# pihat.net
KiCad netlist of a schematic drawn in EAGLE
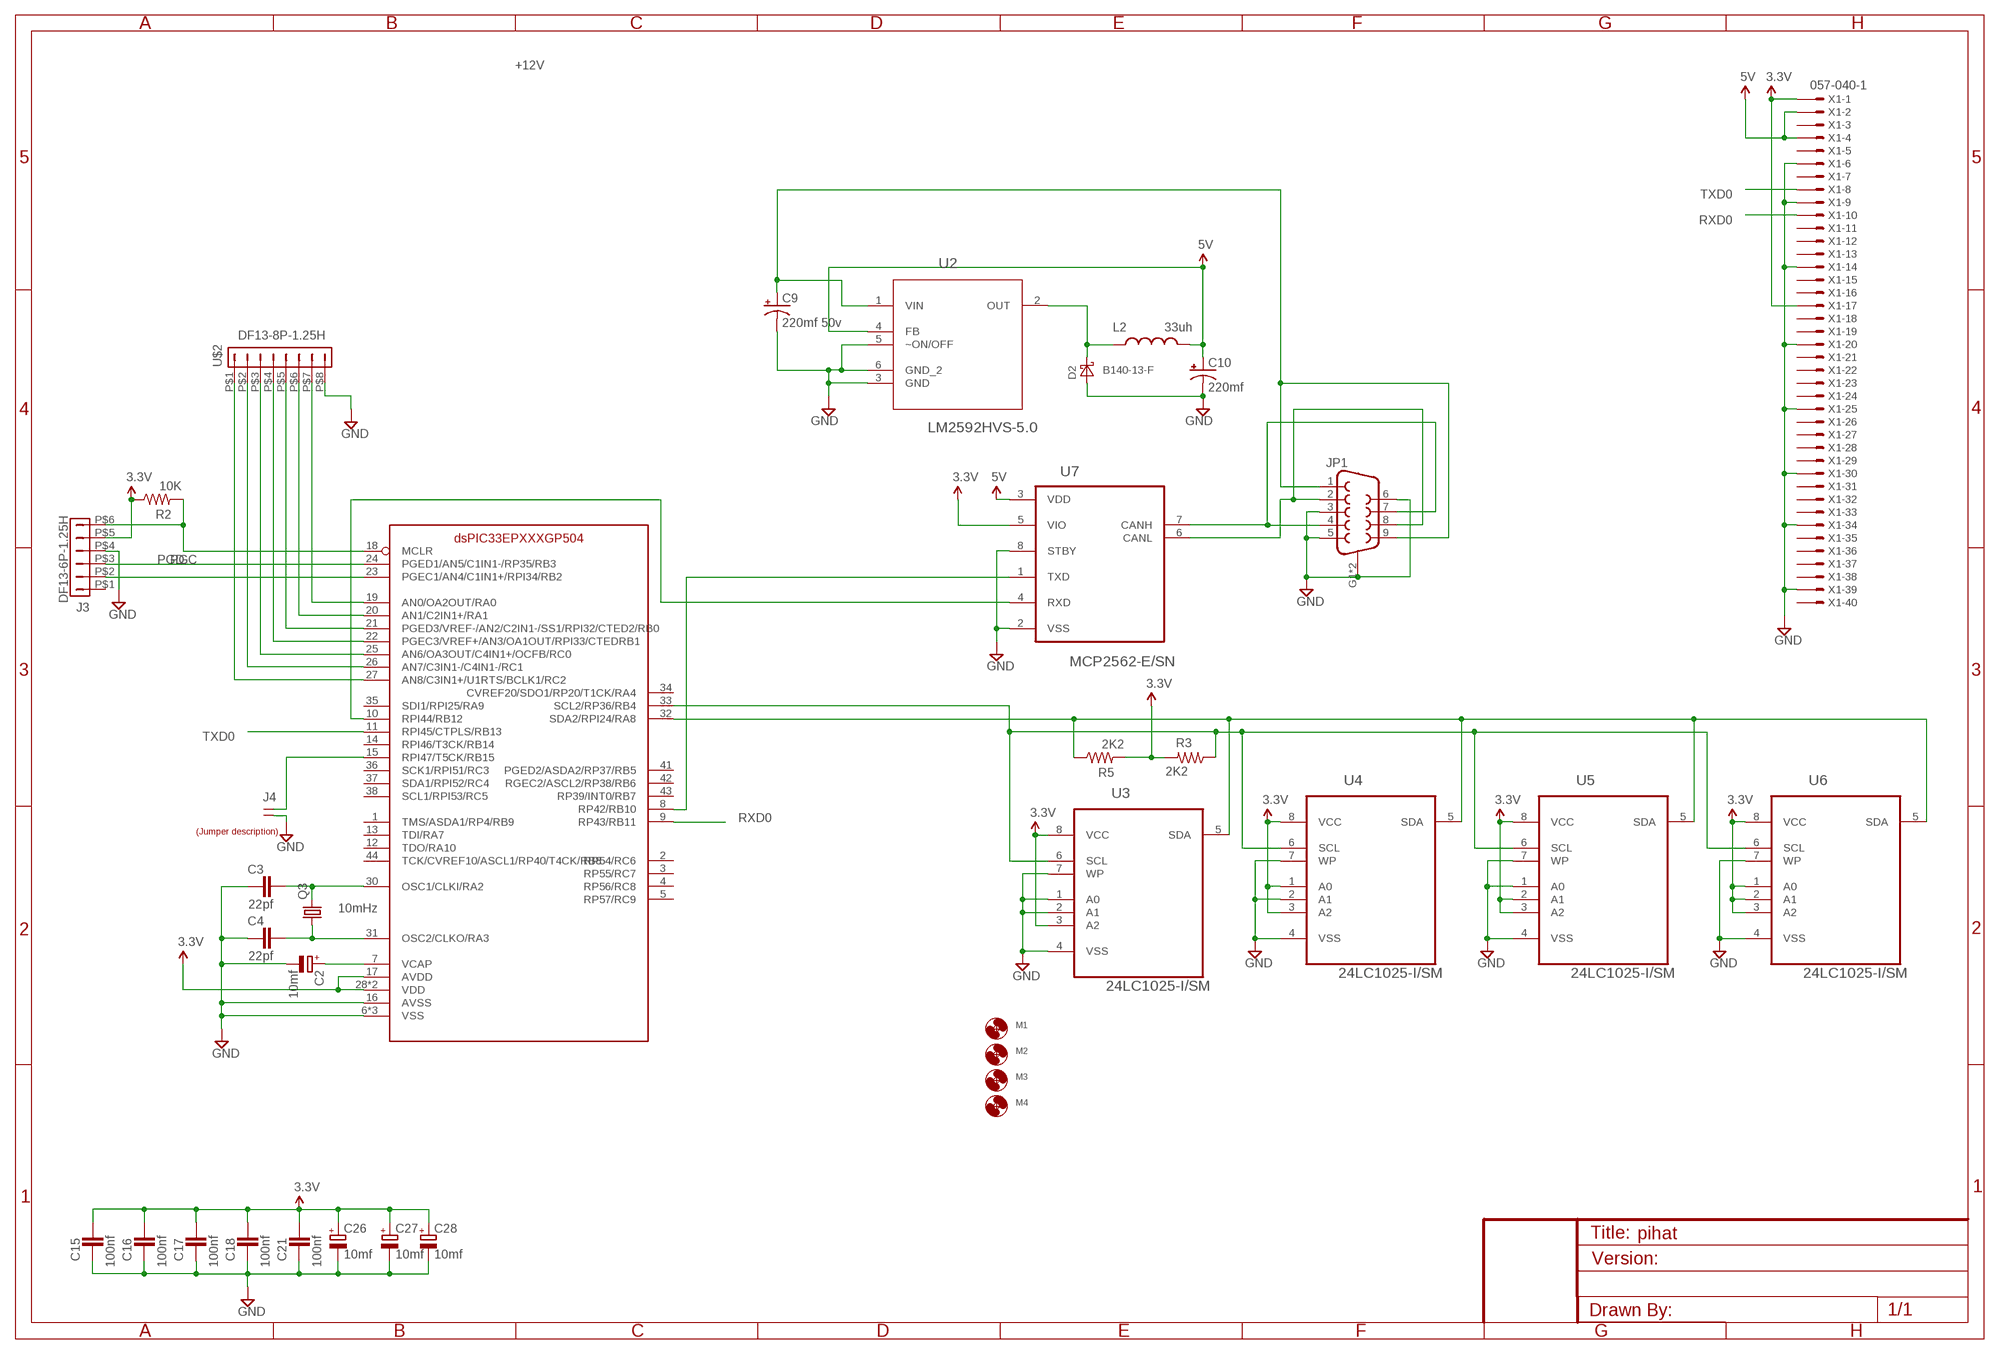
[diagram p0: schematic, sheet 1]

(export (version "E")
  (design (tool "Eeschema 10.0.6"))
  (components
    (comp (ref "C2")
      (value "10mf")
      (footprint "eagle-import:SMC_A")
      (fields (field (name "PARTNO") "T491A106K004AT"))
      (libsource (lib "eagle-import") (part "CAPACITOR_POL-SMC_A"))
    )
    (comp (ref "C3")
      (value "22pf")
      (footprint "eagle-import:C805")
      (fields (field (name "PARTNO") "C0805C220J5GACTU"))
      (libsource (lib "eagle-import") (part "CAPACITOR_NPOL-0805"))
    )
    (comp (ref "C4")
      (value "22pf")
      (footprint "eagle-import:C805")
      (fields (field (name "PARTNO") "C0805C220J5GACTU"))
      (libsource (lib "eagle-import") (part "CAPACITOR_NPOL-0805"))
    )
    (comp (ref "C9")
      (value "220mf 50v")
      (footprint "eagle-import:EIA7343")
      (libsource (lib "eagle-import") (part "CAP_POL7343"))
    )
    (comp (ref "C10")
      (value "220mf")
      (footprint "eagle-import:EIA7343")
      (libsource (lib "eagle-import") (part "CAP_POL7343"))
    )
    (comp (ref "C15")
      (value "100nf")
      (footprint "eagle-import:C805")
      (fields (field (name "PARTNO") "CL21F104ZBCNNNC"))
      (libsource (lib "eagle-import") (part "CAPACITOR_NPOL-0805"))
    )
    (comp (ref "C16")
      (value "100nf")
      (footprint "eagle-import:C805")
      (fields (field (name "PARTNO") "CL21F104ZBCNNNC"))
      (libsource (lib "eagle-import") (part "CAPACITOR_NPOL-0805"))
    )
    (comp (ref "C17")
      (value "100nf")
      (footprint "eagle-import:C805")
      (fields (field (name "PARTNO") "CL21F104ZBCNNNC"))
      (libsource (lib "eagle-import") (part "CAPACITOR_NPOL-0805"))
    )
    (comp (ref "C18")
      (value "100nf")
      (footprint "eagle-import:C805")
      (fields (field (name "PARTNO") "CL21F104ZBCNNNC"))
      (libsource (lib "eagle-import") (part "CAPACITOR_NPOL-0805"))
    )
    (comp (ref "C21")
      (value "100nf")
      (footprint "eagle-import:C805")
      (fields (field (name "PARTNO") "CL21F104ZBCNNNC"))
      (libsource (lib "eagle-import") (part "CAPACITOR_NPOL-0805"))
    )
    (comp (ref "C26")
      (value "10mf")
      (footprint "eagle-import:SMC_A")
      (fields (field (name "PARTNO") "T491A106K004AT"))
      (libsource (lib "eagle-import") (part "CAPACITOR_POL-SMC_A"))
    )
    (comp (ref "C27")
      (value "10mf")
      (footprint "eagle-import:SMC_A")
      (fields (field (name "PARTNO") "T491A106K004AT"))
      (libsource (lib "eagle-import") (part "CAPACITOR_POL-SMC_A"))
    )
    (comp (ref "C28")
      (value "10mf")
      (footprint "eagle-import:SMC_A")
      (fields (field (name "PARTNO") "T491A106K004AT"))
      (libsource (lib "eagle-import") (part "CAPACITOR_POL-SMC_A"))
    )
    (comp (ref "D2")
      (value "B140-13-F")
      (footprint "eagle-import:SMA")
      (libsource (lib "eagle-import") (part "DIODE-SCHOTTKY-SMA"))
    )
    (comp (ref "J3")
      (value "DF13-6P-1.25H")
      (footprint "eagle-import:DF13A-6P-1.25H")
      (fields (field (name "PARTNO") "DF13A-6P-1.25H(20)"))
      (libsource (lib "eagle-import") (part "DF13-6P-1.25H"))
    )
    (comp (ref "J4")
      (value "JUMPER-1X2")
      (footprint "eagle-import:JUMPER-1X2")
      (fields (field (name "PARTNO") "M20-9770246"))
      (libsource (lib "eagle-import") (part "JUMPER-1X2"))
    )
    (comp (ref "JP1")
      (value "DB9MALE")
      (footprint "eagle-import:DB9_MALE")
      (libsource (lib "eagle-import") (part "DB9MALE"))
    )
    (comp (ref "L2")
      (value "33uh")
      (footprint "eagle-import:1812")
      (libsource (lib "eagle-import") (part "INDUCTOR"))
    )
    (comp (ref "M1")
      (value "MOUNT-HOLE2.8")
      (footprint "eagle-import:2,8")
      (libsource (lib "eagle-import") (part "MOUNT-HOLE2.8"))
    )
    (comp (ref "M2")
      (value "MOUNT-HOLE2.8")
      (footprint "eagle-import:2,8")
      (libsource (lib "eagle-import") (part "MOUNT-HOLE2.8"))
    )
    (comp (ref "M3")
      (value "MOUNT-HOLE2.8")
      (footprint "eagle-import:2,8")
      (libsource (lib "eagle-import") (part "MOUNT-HOLE2.8"))
    )
    (comp (ref "M4")
      (value "MOUNT-HOLE2.8")
      (footprint "eagle-import:2,8")
      (libsource (lib "eagle-import") (part "MOUNT-HOLE2.8"))
    )
    (comp (ref "Q3")
      (value "10mHz")
      (footprint "eagle-import:HC49_S")
      (fields (field (name "PARTNO") "ATS100B-E"))
      (libsource (lib "eagle-import") (part "CRYSTALHC49S"))
    )
    (comp (ref "R2")
      (value "10K")
      (footprint "eagle-import:0603-RES")
      (fields (field (name "PARTNO") "RC0603FR-0710KL"))
      (libsource (lib "eagle-import") (part "RESISTOR0603-RES"))
    )
    (comp (ref "R3")
      (value "2K2")
      (footprint "eagle-import:0603-RES")
      (fields (field (name "PARTNO") "RC0603FR-072K2L"))
      (libsource (lib "eagle-import") (part "RESISTOR0603-RES"))
    )
    (comp (ref "R5")
      (value "2K2")
      (footprint "eagle-import:0603-RES")
      (fields (field (name "PARTNO") "RC0603FR-072K2L"))
      (libsource (lib "eagle-import") (part "RESISTOR0603-RES"))
    )
    (comp (ref "U$1")
      (value "LABEL_JUMPER_1X2")
      (footprint "eagle-import:JUMP2_DESC")
      (fields (field (name "OFF") "Normal") (field (name "ON") "Reset"))
      (libsource (lib "eagle-import") (part "LABEL_JUMPER_1X2"))
    )
    (comp (ref "U$2")
      (value "DF13-8P-1.25H")
      (footprint "eagle-import:DF13A-8P-1.25H")
      (libsource (lib "eagle-import") (part "DF13-8P-1.25H"))
    )
    (comp (ref "U1")
      (value "DSPIC33EPXXXGP504")
      (footprint "eagle-import:TQFP44")
      (fields (field (name "PARTNO") "DSPIC33EP512GP504-I/PT"))
      (libsource (lib "eagle-import") (part "DSPIC33EPXXXGP504"))
    )
    (comp (ref "U2")
      (value "LM2592HVS-5.0")
      (footprint "eagle-import:TO170P1435X457-5N")
      (libsource (lib "eagle-import") (part "LM2592HVS-5.0"))
    )
    (comp (ref "U3")
      (value "24LC1025-I/SM")
      (footprint "eagle-import:SOIC8-N_MC")
      (fields (field (name "PARTNO") "24LC1025T-I/SN"))
      (libsource (lib "eagle-import") (part "24LC1025-I/SM"))
    )
    (comp (ref "U4")
      (value "24LC1025-I/SM")
      (footprint "eagle-import:SOIC8-N_MC")
      (fields (field (name "PARTNO") "24LC1025T-I/SN"))
      (libsource (lib "eagle-import") (part "24LC1025-I/SM"))
    )
    (comp (ref "U5")
      (value "24LC1025-I/SM")
      (footprint "eagle-import:SOIC8-N_MC")
      (fields (field (name "PARTNO") "24LC1025T-I/SN"))
      (libsource (lib "eagle-import") (part "24LC1025-I/SM"))
    )
    (comp (ref "U6")
      (value "24LC1025-I/SM")
      (footprint "eagle-import:SOIC8-N_MC")
      (fields (field (name "PARTNO") "24LC1025T-I/SN"))
      (libsource (lib "eagle-import") (part "24LC1025-I/SM"))
    )
    (comp (ref "U7")
      (value "MCP2562-E/SN")
      (footprint "eagle-import:SOIC-8N")
      (libsource (lib "eagle-import") (part "MCP2562-E/SN"))
    )
    (comp (ref "X1")
      (value "057-040-1")
      (footprint "eagle-import:057-040-1")
      (libsource (lib "eagle-import") (part "057-040-1"))
    )
  )
  (nets
    (net (code "1") (name "/+12V") (class "Default")
      (node (ref "C9") (pin "A") (pinfunction "+_A") (pintype "passive"))
      (node (ref "JP1") (pin "1") (pinfunction "1_1") (pintype "passive"))
      (node (ref "JP1") (pin "9") (pinfunction "9_9") (pintype "passive"))
      (node (ref "U2") (pin "1") (pinfunction "VIN_1") (pintype "power_in"))
    )
    (net (code "2") (name "/PGC") (class "Default")
      (node (ref "J3") (pin "P$2") (pinfunction "2_P$2") (pintype "passive"))
      (node (ref "U1") (pin "23") (pinfunction "PGEC1/AN4/C1IN1+/RPI34/RB2_23") (pintype "bidirectional"))
    )
    (net (code "3") (name "/PGD") (class "Default")
      (node (ref "J3") (pin "P$3") (pinfunction "3_P$3") (pintype "passive"))
      (node (ref "U1") (pin "24") (pinfunction "PGED1/AN5/C1IN1-/RP35/RB3_24") (pintype "bidirectional"))
    )
    (net (code "4") (name "/RXD0") (class "Default")
      (node (ref "U1") (pin "9") (pinfunction "RP43/RB11_9") (pintype "bidirectional"))
      (node (ref "X1") (pin "10") (pinfunction "S_10") (pintype "passive"))
    )
    (net (code "5") (name "/TXD0") (class "Default")
      (node (ref "U1") (pin "11") (pinfunction "RPI45/CTPLS/RB13_11") (pintype "bidirectional"))
      (node (ref "X1") (pin "8") (pinfunction "S_8") (pintype "passive"))
    )
    (net (code "6") (name "3.3V") (class "Default")
      (node (ref "C15") (pin "1") (pinfunction "1_1") (pintype "passive"))
      (node (ref "C16") (pin "1") (pinfunction "1_1") (pintype "passive"))
      (node (ref "C17") (pin "1") (pinfunction "1_1") (pintype "passive"))
      (node (ref "C18") (pin "1") (pinfunction "1_1") (pintype "passive"))
      (node (ref "C21") (pin "1") (pinfunction "1_1") (pintype "passive"))
      (node (ref "C26") (pin "+") (pinfunction "+_+") (pintype "passive"))
      (node (ref "C27") (pin "+") (pinfunction "+_+") (pintype "passive"))
      (node (ref "C28") (pin "+") (pinfunction "+_+") (pintype "passive"))
      (node (ref "J3") (pin "P$5") (pinfunction "5_P$5") (pintype "passive"))
      (node (ref "R2") (pin "1") (pinfunction "1_1") (pintype "passive"))
      (node (ref "R3") (pin "2") (pinfunction "2_2") (pintype "passive"))
      (node (ref "R5") (pin "2") (pinfunction "2_2") (pintype "passive"))
      (node (ref "U1") (pin "17") (pinfunction "AVDD_17") (pintype "bidirectional"))
      (node (ref "U1") (pin "28") (pinfunction "VDD_28") (pintype "bidirectional"))
      (node (ref "U1") (pin "40") (pinfunction "VDD_40") (pintype "bidirectional"))
      (node (ref "U3") (pin "3") (pinfunction "A2_3") (pintype "input"))
      (node (ref "U3") (pin "8") (pinfunction "VCC_8") (pintype "power_in"))
      (node (ref "U4") (pin "1") (pinfunction "A0_1") (pintype "input"))
      (node (ref "U4") (pin "3") (pinfunction "A2_3") (pintype "input"))
      (node (ref "U4") (pin "8") (pinfunction "VCC_8") (pintype "power_in"))
      (node (ref "U5") (pin "2") (pinfunction "A1_2") (pintype "input"))
      (node (ref "U5") (pin "3") (pinfunction "A2_3") (pintype "input"))
      (node (ref "U5") (pin "8") (pinfunction "VCC_8") (pintype "power_in"))
      (node (ref "U6") (pin "1") (pinfunction "A0_1") (pintype "input"))
      (node (ref "U6") (pin "2") (pinfunction "A1_2") (pintype "input"))
      (node (ref "U6") (pin "3") (pinfunction "A2_3") (pintype "input"))
      (node (ref "U6") (pin "8") (pinfunction "VCC_8") (pintype "power_in"))
      (node (ref "U7") (pin "5") (pinfunction "VIO_5") (pintype "power_in"))
      (node (ref "X1") (pin "1") (pinfunction "S_1") (pintype "passive"))
      (node (ref "X1") (pin "17") (pinfunction "S_17") (pintype "passive"))
    )
    (net (code "7") (name "5V") (class "Default")
      (node (ref "C10") (pin "A") (pinfunction "+_A") (pintype "passive"))
      (node (ref "L2") (pin "2") (pinfunction "2_2") (pintype "passive"))
      (node (ref "U2") (pin "4") (pinfunction "FB_4") (pintype "input"))
      (node (ref "U7") (pin "3") (pinfunction "VDD_3") (pintype "power_in"))
      (node (ref "X1") (pin "2") (pinfunction "S_2") (pintype "passive"))
      (node (ref "X1") (pin "4") (pinfunction "S_4") (pintype "passive"))
    )
    (net (code "8") (name "GND") (class "Default")
      (node (ref "C10") (pin "C") (pinfunction "-_C") (pintype "passive"))
      (node (ref "C15") (pin "2") (pinfunction "2_2") (pintype "passive"))
      (node (ref "C16") (pin "2") (pinfunction "2_2") (pintype "passive"))
      (node (ref "C17") (pin "2") (pinfunction "2_2") (pintype "passive"))
      (node (ref "C18") (pin "2") (pinfunction "2_2") (pintype "passive"))
      (node (ref "C2") (pin "-") (pinfunction "-_-") (pintype "passive"))
      (node (ref "C21") (pin "2") (pinfunction "2_2") (pintype "passive"))
      (node (ref "C26") (pin "-") (pinfunction "-_-") (pintype "passive"))
      (node (ref "C27") (pin "-") (pinfunction "-_-") (pintype "passive"))
      (node (ref "C28") (pin "-") (pinfunction "-_-") (pintype "passive"))
      (node (ref "C3") (pin "2") (pinfunction "2_2") (pintype "passive"))
      (node (ref "C4") (pin "2") (pinfunction "2_2") (pintype "passive"))
      (node (ref "C9") (pin "C") (pinfunction "-_C") (pintype "passive"))
      (node (ref "D2") (pin "A") (pinfunction "A_A") (pintype "passive"))
      (node (ref "J3") (pin "P$4") (pinfunction "4_P$4") (pintype "passive"))
      (node (ref "J4") (pin "2") (pinfunction "2_2") (pintype "bidirectional"))
      (node (ref "JP1") (pin "3") (pinfunction "3_3") (pintype "passive"))
      (node (ref "JP1") (pin "5") (pinfunction "5_5") (pintype "passive"))
      (node (ref "JP1") (pin "6") (pinfunction "6_6") (pintype "passive"))
      (node (ref "JP1") (pin "G1") (pinfunction "SHIELD_G1") (pintype "power_in"))
      (node (ref "JP1") (pin "G2") (pinfunction "SHIELD_G2") (pintype "power_in"))
      (node (ref "U$2") (pin "P$8") (pinfunction "8_P$8") (pintype "passive"))
      (node (ref "U1") (pin "16") (pinfunction "AVSS_16") (pintype "bidirectional"))
      (node (ref "U1") (pin "29") (pinfunction "VSS_29") (pintype "bidirectional"))
      (node (ref "U1") (pin "39") (pinfunction "VSS_39") (pintype "bidirectional"))
      (node (ref "U1") (pin "6") (pinfunction "VSS_6") (pintype "bidirectional"))
      (node (ref "U2") (pin "3") (pinfunction "GND_3") (pintype "passive"))
      (node (ref "U2") (pin "5") (pinfunction "~{ON/OFF}_5") (pintype "input"))
      (node (ref "U2") (pin "6") (pinfunction "GND_2_6") (pintype "passive"))
      (node (ref "U3") (pin "1") (pinfunction "A0_1") (pintype "input"))
      (node (ref "U3") (pin "2") (pinfunction "A1_2") (pintype "input"))
      (node (ref "U3") (pin "4") (pinfunction "VSS_4") (pintype "passive"))
      (node (ref "U3") (pin "7") (pinfunction "WP_7") (pintype "input"))
      (node (ref "U4") (pin "2") (pinfunction "A1_2") (pintype "input"))
      (node (ref "U4") (pin "4") (pinfunction "VSS_4") (pintype "passive"))
      (node (ref "U4") (pin "7") (pinfunction "WP_7") (pintype "input"))
      (node (ref "U5") (pin "1") (pinfunction "A0_1") (pintype "input"))
      (node (ref "U5") (pin "4") (pinfunction "VSS_4") (pintype "passive"))
      (node (ref "U5") (pin "7") (pinfunction "WP_7") (pintype "input"))
      (node (ref "U6") (pin "4") (pinfunction "VSS_4") (pintype "passive"))
      (node (ref "U6") (pin "7") (pinfunction "WP_7") (pintype "input"))
      (node (ref "U7") (pin "2") (pinfunction "VSS_2") (pintype "power_in"))
      (node (ref "U7") (pin "8") (pinfunction "STBY_8") (pintype "input"))
      (node (ref "X1") (pin "14") (pinfunction "S_14") (pintype "passive"))
      (node (ref "X1") (pin "20") (pinfunction "S_20") (pintype "passive"))
      (node (ref "X1") (pin "25") (pinfunction "S_25") (pintype "passive"))
      (node (ref "X1") (pin "30") (pinfunction "S_30") (pintype "passive"))
      (node (ref "X1") (pin "34") (pinfunction "S_34") (pintype "passive"))
      (node (ref "X1") (pin "39") (pinfunction "S_39") (pintype "passive"))
      (node (ref "X1") (pin "6") (pinfunction "S_6") (pintype "passive"))
      (node (ref "X1") (pin "9") (pinfunction "S_9") (pintype "passive"))
    )
    (net (code "9") (name "Net-(J3-6)") (class "Default")
      (node (ref "J3") (pin "P$6") (pinfunction "6_P$6") (pintype "passive"))
      (node (ref "R2") (pin "2") (pinfunction "2_2") (pintype "passive"))
      (node (ref "U1") (pin "18") (pinfunction "MCLR_18") (pintype "input"))
    )
    (net (code "10") (name "Net-(U$2-1)") (class "Default")
      (node (ref "U$2") (pin "P$1") (pinfunction "1_P$1") (pintype "passive"))
      (node (ref "U1") (pin "27") (pinfunction "AN8/C3IN1+/U1RTS/BCLK1/RC2_27") (pintype "bidirectional"))
    )
    (net (code "11") (name "Net-(U$2-2)") (class "Default")
      (node (ref "U$2") (pin "P$2") (pinfunction "2_P$2") (pintype "passive"))
      (node (ref "U1") (pin "26") (pinfunction "AN7/C3IN1-/C4IN1-/RC1_26") (pintype "bidirectional"))
    )
    (net (code "12") (name "Net-(U$2-3)") (class "Default")
      (node (ref "U$2") (pin "P$3") (pinfunction "3_P$3") (pintype "passive"))
      (node (ref "U1") (pin "25") (pinfunction "AN6/OA3OUT/C4IN1+/OCFB/RC0_25") (pintype "bidirectional"))
    )
    (net (code "13") (name "Net-(U$2-4)") (class "Default")
      (node (ref "U$2") (pin "P$4") (pinfunction "4_P$4") (pintype "passive"))
      (node (ref "U1") (pin "22") (pinfunction "PGEC3/VREF+/AN3/OA1OUT/RPI33/CTEDRB1_22") (pintype "bidirectional"))
    )
    (net (code "14") (name "Net-(U$2-5)") (class "Default")
      (node (ref "U$2") (pin "P$5") (pinfunction "5_P$5") (pintype "passive"))
      (node (ref "U1") (pin "21") (pinfunction "PGED3/VREF-/AN2/C2IN1-/SS1/RPI32/CTED2/RB0_21") (pintype "bidirectional"))
    )
    (net (code "15") (name "Net-(U$2-6)") (class "Default")
      (node (ref "U$2") (pin "P$6") (pinfunction "6_P$6") (pintype "passive"))
      (node (ref "U1") (pin "20") (pinfunction "AN1/C2IN1+/RA1_20") (pintype "bidirectional"))
    )
    (net (code "16") (name "Net-(U$2-7)") (class "Default")
      (node (ref "U$2") (pin "P$7") (pinfunction "7_P$7") (pintype "passive"))
      (node (ref "U1") (pin "19") (pinfunction "AN0/OA2OUT/RA0_19") (pintype "bidirectional"))
    )
    (net (code "17") (name "Net-(U1-OSC1{slash}CLKI{slash}RA2)") (class "Default")
      (node (ref "C3") (pin "1") (pinfunction "1_1") (pintype "passive"))
      (node (ref "Q3") (pin "2") (pinfunction "2_2") (pintype "passive"))
      (node (ref "U1") (pin "30") (pinfunction "OSC1/CLKI/RA2_30") (pintype "bidirectional"))
    )
    (net (code "18") (name "Net-(U1-OSC2{slash}CLKO{slash}RA3)") (class "Default")
      (node (ref "C4") (pin "1") (pinfunction "1_1") (pintype "passive"))
      (node (ref "Q3") (pin "1") (pinfunction "1_1") (pintype "passive"))
      (node (ref "U1") (pin "31") (pinfunction "OSC2/CLKO/RA3_31") (pintype "bidirectional"))
    )
    (net (code "19") (name "Net-(U1-RP42{slash}RB10)") (class "Default")
      (node (ref "U1") (pin "8") (pinfunction "RP42/RB10_8") (pintype "bidirectional"))
      (node (ref "U7") (pin "1") (pinfunction "TXD_1") (pintype "input"))
    )
    (net (code "20") (name "Net-(U1-RPI44{slash}RB12)") (class "Default")
      (node (ref "U1") (pin "10") (pinfunction "RPI44/RB12_10") (pintype "bidirectional"))
      (node (ref "U7") (pin "4") (pinfunction "RXD_4") (pintype "output"))
    )
    (net (code "21") (name "Net-(U1-RPI47{slash}T5CK{slash}RB15)") (class "Default")
      (node (ref "J4") (pin "1") (pinfunction "1_1") (pintype "bidirectional"))
      (node (ref "U1") (pin "15") (pinfunction "RPI47/T5CK/RB15_15") (pintype "bidirectional"))
    )
    (net (code "22") (name "Net-(U1-SCL2{slash}RP36{slash}RB4)") (class "Default")
      (node (ref "R3") (pin "1") (pinfunction "1_1") (pintype "passive"))
      (node (ref "U1") (pin "33") (pinfunction "SCL2/RP36/RB4_33") (pintype "bidirectional"))
      (node (ref "U3") (pin "6") (pinfunction "SCL_6") (pintype "input"))
      (node (ref "U4") (pin "6") (pinfunction "SCL_6") (pintype "input"))
      (node (ref "U5") (pin "6") (pinfunction "SCL_6") (pintype "input"))
      (node (ref "U6") (pin "6") (pinfunction "SCL_6") (pintype "input"))
    )
    (net (code "23") (name "Net-(U1-SDA2{slash}RPI24{slash}RA8)") (class "Default")
      (node (ref "R5") (pin "1") (pinfunction "1_1") (pintype "passive"))
      (node (ref "U1") (pin "32") (pinfunction "SDA2/RPI24/RA8_32") (pintype "bidirectional"))
      (node (ref "U3") (pin "5") (pinfunction "SDA_5") (pintype "bidirectional"))
      (node (ref "U4") (pin "5") (pinfunction "SDA_5") (pintype "bidirectional"))
      (node (ref "U5") (pin "5") (pinfunction "SDA_5") (pintype "bidirectional"))
      (node (ref "U6") (pin "5") (pinfunction "SDA_5") (pintype "bidirectional"))
    )
    (net (code "24") (name "Net-(U1-VCAP)") (class "Default")
      (node (ref "C2") (pin "+") (pinfunction "+_+") (pintype "passive"))
      (node (ref "U1") (pin "7") (pinfunction "VCAP_7") (pintype "bidirectional"))
    )
    (net (code "25") (name "Net-(U2-OUT)") (class "Default")
      (node (ref "D2") (pin "C") (pinfunction "C_C") (pintype "passive"))
      (node (ref "L2") (pin "1") (pinfunction "1_1") (pintype "passive"))
      (node (ref "U2") (pin "2") (pinfunction "OUT_2") (pintype "output"))
    )
    (net (code "26") (name "Net-(U7-CANH)") (class "Default")
      (node (ref "JP1") (pin "4") (pinfunction "4_4") (pintype "passive"))
      (node (ref "JP1") (pin "7") (pinfunction "7_7") (pintype "passive"))
      (node (ref "U7") (pin "7") (pinfunction "CANH_7") (pintype "bidirectional"))
    )
    (net (code "27") (name "Net-(U7-CANL)") (class "Default")
      (node (ref "JP1") (pin "2") (pinfunction "2_2") (pintype "passive"))
      (node (ref "JP1") (pin "8") (pinfunction "8_8") (pintype "passive"))
      (node (ref "U7") (pin "6") (pinfunction "CANL_6") (pintype "bidirectional"))
    )
    (net (code "28") (name "unconnected-(J3-1-PadP$1)") (class "Default")
      (node (ref "J3") (pin "P$1") (pinfunction "1_P$1") (pintype "passive"))
    )
    (net (code "29") (name "unconnected-(U1-CVREF20{slash}SDO1{slash}RP20{slash}T1CK{slash}RA4-Pad34)") (class "Default")
      (node (ref "U1") (pin "34") (pinfunction "CVREF20/SDO1/RP20/T1CK/RA4_34") (pintype "bidirectional"))
    )
    (net (code "30") (name "unconnected-(U1-PGED2{slash}ASDA2{slash}RP37{slash}RB5-Pad41)") (class "Default")
      (node (ref "U1") (pin "41") (pinfunction "PGED2/ASDA2/RP37/RB5_41") (pintype "bidirectional"))
    )
    (net (code "31") (name "unconnected-(U1-RGEC2{slash}ASCL2{slash}RP38{slash}RB6-Pad42)") (class "Default")
      (node (ref "U1") (pin "42") (pinfunction "RGEC2/ASCL2/RP38/RB6_42") (pintype "bidirectional"))
    )
    (net (code "32") (name "unconnected-(U1-RP39{slash}INT0{slash}RB7-Pad43)") (class "Default")
      (node (ref "U1") (pin "43") (pinfunction "RP39/INT0/RB7_43") (pintype "bidirectional"))
    )
    (net (code "33") (name "unconnected-(U1-RP54{slash}RC6-Pad2)") (class "Default")
      (node (ref "U1") (pin "2") (pinfunction "RP54/RC6_2") (pintype "bidirectional"))
    )
    (net (code "34") (name "unconnected-(U1-RP55{slash}RC7-Pad3)") (class "Default")
      (node (ref "U1") (pin "3") (pinfunction "RP55/RC7_3") (pintype "bidirectional"))
    )
    (net (code "35") (name "unconnected-(U1-RP56{slash}RC8-Pad4)") (class "Default")
      (node (ref "U1") (pin "4") (pinfunction "RP56/RC8_4") (pintype "bidirectional"))
    )
    (net (code "36") (name "unconnected-(U1-RP57{slash}RC9-Pad5)") (class "Default")
      (node (ref "U1") (pin "5") (pinfunction "RP57/RC9_5") (pintype "bidirectional"))
    )
    (net (code "37") (name "unconnected-(U1-RPI46{slash}T3CK{slash}RB14-Pad14)") (class "Default")
      (node (ref "U1") (pin "14") (pinfunction "RPI46/T3CK/RB14_14") (pintype "bidirectional"))
    )
    (net (code "38") (name "unconnected-(U1-SCK1{slash}RPI51{slash}RC3-Pad36)") (class "Default")
      (node (ref "U1") (pin "36") (pinfunction "SCK1/RPI51/RC3_36") (pintype "bidirectional"))
    )
    (net (code "39") (name "unconnected-(U1-SCL1{slash}RPI53{slash}RC5-Pad38)") (class "Default")
      (node (ref "U1") (pin "38") (pinfunction "SCL1/RPI53/RC5_38") (pintype "bidirectional"))
    )
    (net (code "40") (name "unconnected-(U1-SDA1{slash}RPI52{slash}RC4-Pad37)") (class "Default")
      (node (ref "U1") (pin "37") (pinfunction "SDA1/RPI52/RC4_37") (pintype "bidirectional"))
    )
    (net (code "41") (name "unconnected-(U1-SDI1{slash}RPI25{slash}RA9-Pad35)") (class "Default")
      (node (ref "U1") (pin "35") (pinfunction "SDI1/RPI25/RA9_35") (pintype "bidirectional"))
    )
    (net (code "42") (name "unconnected-(U1-TCK{slash}CVREF10{slash}ASCL1{slash}RP40{slash}T4CK{slash}RB8-Pad44)") (class "Default")
      (node (ref "U1") (pin "44") (pinfunction "TCK/CVREF10/ASCL1/RP40/T4CK/RB8_44") (pintype "bidirectional"))
    )
    (net (code "43") (name "unconnected-(U1-TDI{slash}RA7-Pad13)") (class "Default")
      (node (ref "U1") (pin "13") (pinfunction "TDI/RA7_13") (pintype "bidirectional"))
    )
    (net (code "44") (name "unconnected-(U1-TDO{slash}RA10-Pad12)") (class "Default")
      (node (ref "U1") (pin "12") (pinfunction "TDO/RA10_12") (pintype "bidirectional"))
    )
    (net (code "45") (name "unconnected-(U1-TMS{slash}ASDA1{slash}RP4{slash}RB9-Pad1)") (class "Default")
      (node (ref "U1") (pin "1") (pinfunction "TMS/ASDA1/RP4/RB9_1") (pintype "bidirectional"))
    )
    (net (code "46") (name "unconnected-(X1AA-S-Pad33)") (class "Default")
      (node (ref "X1") (pin "33") (pinfunction "S_33") (pintype "passive"))
    )
    (net (code "47") (name "unconnected-(X1AC-S-Pad35)") (class "Default")
      (node (ref "X1") (pin "35") (pinfunction "S_35") (pintype "passive"))
    )
    (net (code "48") (name "unconnected-(X1AD-S-Pad36)") (class "Default")
      (node (ref "X1") (pin "36") (pinfunction "S_36") (pintype "passive"))
    )
    (net (code "49") (name "unconnected-(X1AE-S-Pad37)") (class "Default")
      (node (ref "X1") (pin "37") (pinfunction "S_37") (pintype "passive"))
    )
    (net (code "50") (name "unconnected-(X1AF-S-Pad38)") (class "Default")
      (node (ref "X1") (pin "38") (pinfunction "S_38") (pintype "passive"))
    )
    (net (code "51") (name "unconnected-(X1AI-S-Pad40)") (class "Default")
      (node (ref "X1") (pin "40") (pinfunction "S_40") (pintype "passive"))
    )
    (net (code "52") (name "unconnected-(X1AJ-S-Pad5)") (class "Default")
      (node (ref "X1") (pin "5") (pinfunction "S_5") (pintype "passive"))
    )
    (net (code "53") (name "unconnected-(X1AL-S-Pad7)") (class "Default")
      (node (ref "X1") (pin "7") (pinfunction "S_7") (pintype "passive"))
    )
    (net (code "54") (name "unconnected-(X1C-S-Pad11)") (class "Default")
      (node (ref "X1") (pin "11") (pinfunction "S_11") (pintype "passive"))
    )
    (net (code "55") (name "unconnected-(X1D-S-Pad12)") (class "Default")
      (node (ref "X1") (pin "12") (pinfunction "S_12") (pintype "passive"))
    )
    (net (code "56") (name "unconnected-(X1E-S-Pad13)") (class "Default")
      (node (ref "X1") (pin "13") (pinfunction "S_13") (pintype "passive"))
    )
    (net (code "57") (name "unconnected-(X1G-S-Pad15)") (class "Default")
      (node (ref "X1") (pin "15") (pinfunction "S_15") (pintype "passive"))
    )
    (net (code "58") (name "unconnected-(X1H-S-Pad16)") (class "Default")
      (node (ref "X1") (pin "16") (pinfunction "S_16") (pintype "passive"))
    )
    (net (code "59") (name "unconnected-(X1J-S-Pad18)") (class "Default")
      (node (ref "X1") (pin "18") (pinfunction "S_18") (pintype "passive"))
    )
    (net (code "60") (name "unconnected-(X1K-S-Pad19)") (class "Default")
      (node (ref "X1") (pin "19") (pinfunction "S_19") (pintype "passive"))
    )
    (net (code "61") (name "unconnected-(X1N-S-Pad21)") (class "Default")
      (node (ref "X1") (pin "21") (pinfunction "S_21") (pintype "passive"))
    )
    (net (code "62") (name "unconnected-(X1O-S-Pad22)") (class "Default")
      (node (ref "X1") (pin "22") (pinfunction "S_22") (pintype "passive"))
    )
    (net (code "63") (name "unconnected-(X1P-S-Pad23)") (class "Default")
      (node (ref "X1") (pin "23") (pinfunction "S_23") (pintype "passive"))
    )
    (net (code "64") (name "unconnected-(X1Q-S-Pad24)") (class "Default")
      (node (ref "X1") (pin "24") (pinfunction "S_24") (pintype "passive"))
    )
    (net (code "65") (name "unconnected-(X1S-S-Pad26)") (class "Default")
      (node (ref "X1") (pin "26") (pinfunction "S_26") (pintype "passive"))
    )
    (net (code "66") (name "unconnected-(X1T-S-Pad27)") (class "Default")
      (node (ref "X1") (pin "27") (pinfunction "S_27") (pintype "passive"))
    )
    (net (code "67") (name "unconnected-(X1U-S-Pad28)") (class "Default")
      (node (ref "X1") (pin "28") (pinfunction "S_28") (pintype "passive"))
    )
    (net (code "68") (name "unconnected-(X1V-S-Pad29)") (class "Default")
      (node (ref "X1") (pin "29") (pinfunction "S_29") (pintype "passive"))
    )
    (net (code "69") (name "unconnected-(X1W-S-Pad3)") (class "Default")
      (node (ref "X1") (pin "3") (pinfunction "S_3") (pintype "passive"))
    )
    (net (code "70") (name "unconnected-(X1Y-S-Pad31)") (class "Default")
      (node (ref "X1") (pin "31") (pinfunction "S_31") (pintype "passive"))
    )
    (net (code "71") (name "unconnected-(X1Z-S-Pad32)") (class "Default")
      (node (ref "X1") (pin "32") (pinfunction "S_32") (pintype "passive"))
    )
  )
)
